# bb8_v3.net
KiCad netlist of a schematic drawn in Altium Designer
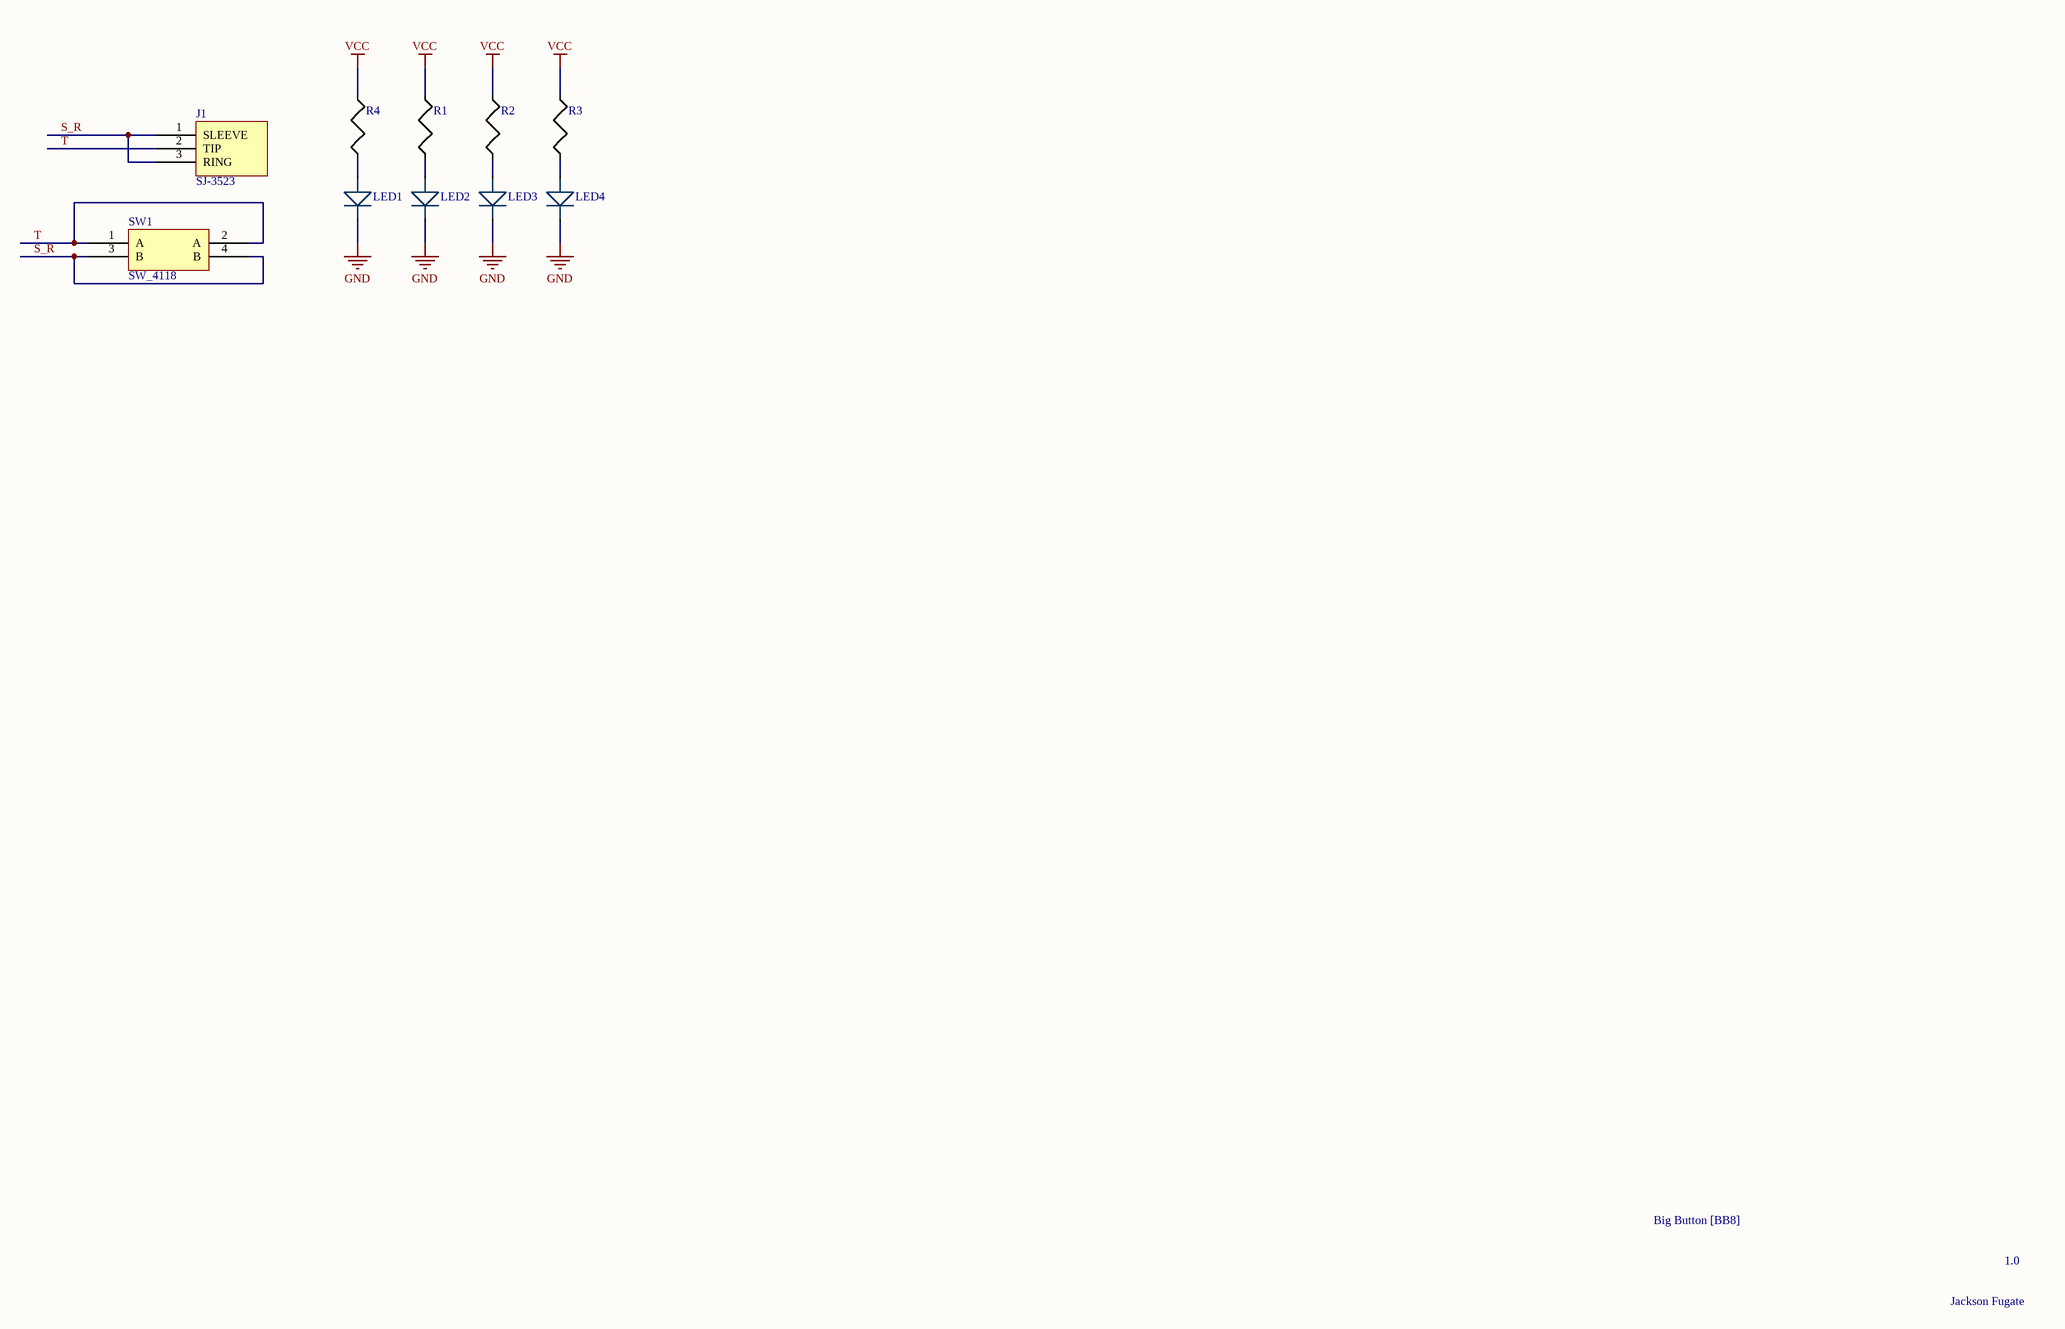
[diagram p0: bb8_v3.SchDoc]

(export (version "E")
  (design (tool "Eeschema 10.0.6"))
  (components
    (comp (ref "J1")
      (value "SJ-3523")
      (footprint "SJ-352X")
      (libsource (lib "JF_master_lib") (part "SJ-3523"))
    )
    (comp (ref "LED1")
      (value "LED?")
      (footprint "LED_TH")
      (libsource (lib "JF_master_lib") (part "LED_GENERIC"))
    )
    (comp (ref "LED2")
      (value "LED?")
      (footprint "LED_TH")
      (libsource (lib "JF_master_lib") (part "LED_GENERIC"))
    )
    (comp (ref "LED3")
      (value "LED?")
      (footprint "LED_TH")
      (libsource (lib "JF_master_lib") (part "LED_GENERIC"))
    )
    (comp (ref "LED4")
      (value "LED?")
      (footprint "LED_TH")
      (libsource (lib "JF_master_lib") (part "LED_GENERIC"))
    )
    (comp (ref "R1")
      (value "RES_GENERIC")
      (footprint "RES_TH")
      (libsource (lib "JF_master_lib") (part "RES_GENERIC"))
    )
    (comp (ref "R2")
      (value "RES_GENERIC")
      (footprint "RES_TH")
      (libsource (lib "JF_master_lib") (part "RES_GENERIC"))
    )
    (comp (ref "R3")
      (value "RES_GENERIC")
      (footprint "RES_TH")
      (libsource (lib "JF_master_lib") (part "RES_GENERIC"))
    )
    (comp (ref "R4")
      (value "RES_GENERIC")
      (footprint "RES_TH")
      (libsource (lib "JF_master_lib") (part "RES_GENERIC"))
    )
    (comp (ref "SW1")
      (value "SW_4118")
      (footprint "SW_4118")
      (libsource (lib "JF_master_lib") (part "SW_4118"))
    )
  )
  (nets
    (net (code "1") (name "/S_R") (class "Default")
      (node (ref "J1") (pin "1") (pinfunction "SLEEVE_1") (pintype "passive"))
      (node (ref "J1") (pin "3") (pinfunction "RING_3") (pintype "passive"))
      (node (ref "SW1") (pin "3") (pinfunction "B_3") (pintype "passive"))
      (node (ref "SW1") (pin "4") (pinfunction "B_4") (pintype "passive"))
    )
    (net (code "2") (name "/T") (class "Default")
      (node (ref "J1") (pin "2") (pinfunction "TIP_2") (pintype "passive"))
      (node (ref "SW1") (pin "1") (pinfunction "A_1") (pintype "passive"))
      (node (ref "SW1") (pin "2") (pinfunction "A_2") (pintype "passive"))
    )
    (net (code "3") (name "GND") (class "Default")
      (node (ref "LED1") (pin "2") (pinfunction "2_2") (pintype "passive"))
      (node (ref "LED2") (pin "2") (pinfunction "2_2") (pintype "passive"))
      (node (ref "LED3") (pin "2") (pinfunction "2_2") (pintype "passive"))
      (node (ref "LED4") (pin "2") (pinfunction "2_2") (pintype "passive"))
    )
    (net (code "4") (name "Net-(LED1-Pad1)") (class "Default")
      (node (ref "LED1") (pin "1") (pinfunction "1_1") (pintype "passive"))
      (node (ref "R4") (pin "2") (pinfunction "2_2") (pintype "passive"))
    )
    (net (code "5") (name "Net-(LED2-Pad1)") (class "Default")
      (node (ref "LED2") (pin "1") (pinfunction "1_1") (pintype "passive"))
      (node (ref "R1") (pin "2") (pinfunction "2_2") (pintype "passive"))
    )
    (net (code "6") (name "Net-(LED3-Pad1)") (class "Default")
      (node (ref "LED3") (pin "1") (pinfunction "1_1") (pintype "passive"))
      (node (ref "R2") (pin "2") (pinfunction "2_2") (pintype "passive"))
    )
    (net (code "7") (name "Net-(LED4-Pad1)") (class "Default")
      (node (ref "LED4") (pin "1") (pinfunction "1_1") (pintype "passive"))
      (node (ref "R3") (pin "2") (pinfunction "2_2") (pintype "passive"))
    )
    (net (code "8") (name "VCC") (class "Default")
      (node (ref "R1") (pin "1") (pinfunction "1_1") (pintype "passive"))
      (node (ref "R2") (pin "1") (pinfunction "1_1") (pintype "passive"))
      (node (ref "R3") (pin "1") (pinfunction "1_1") (pintype "passive"))
      (node (ref "R4") (pin "1") (pinfunction "1_1") (pintype "passive"))
    )
  )
)
